# USB_OTG.net
KiCad netlist of a schematic drawn in Altium Designer
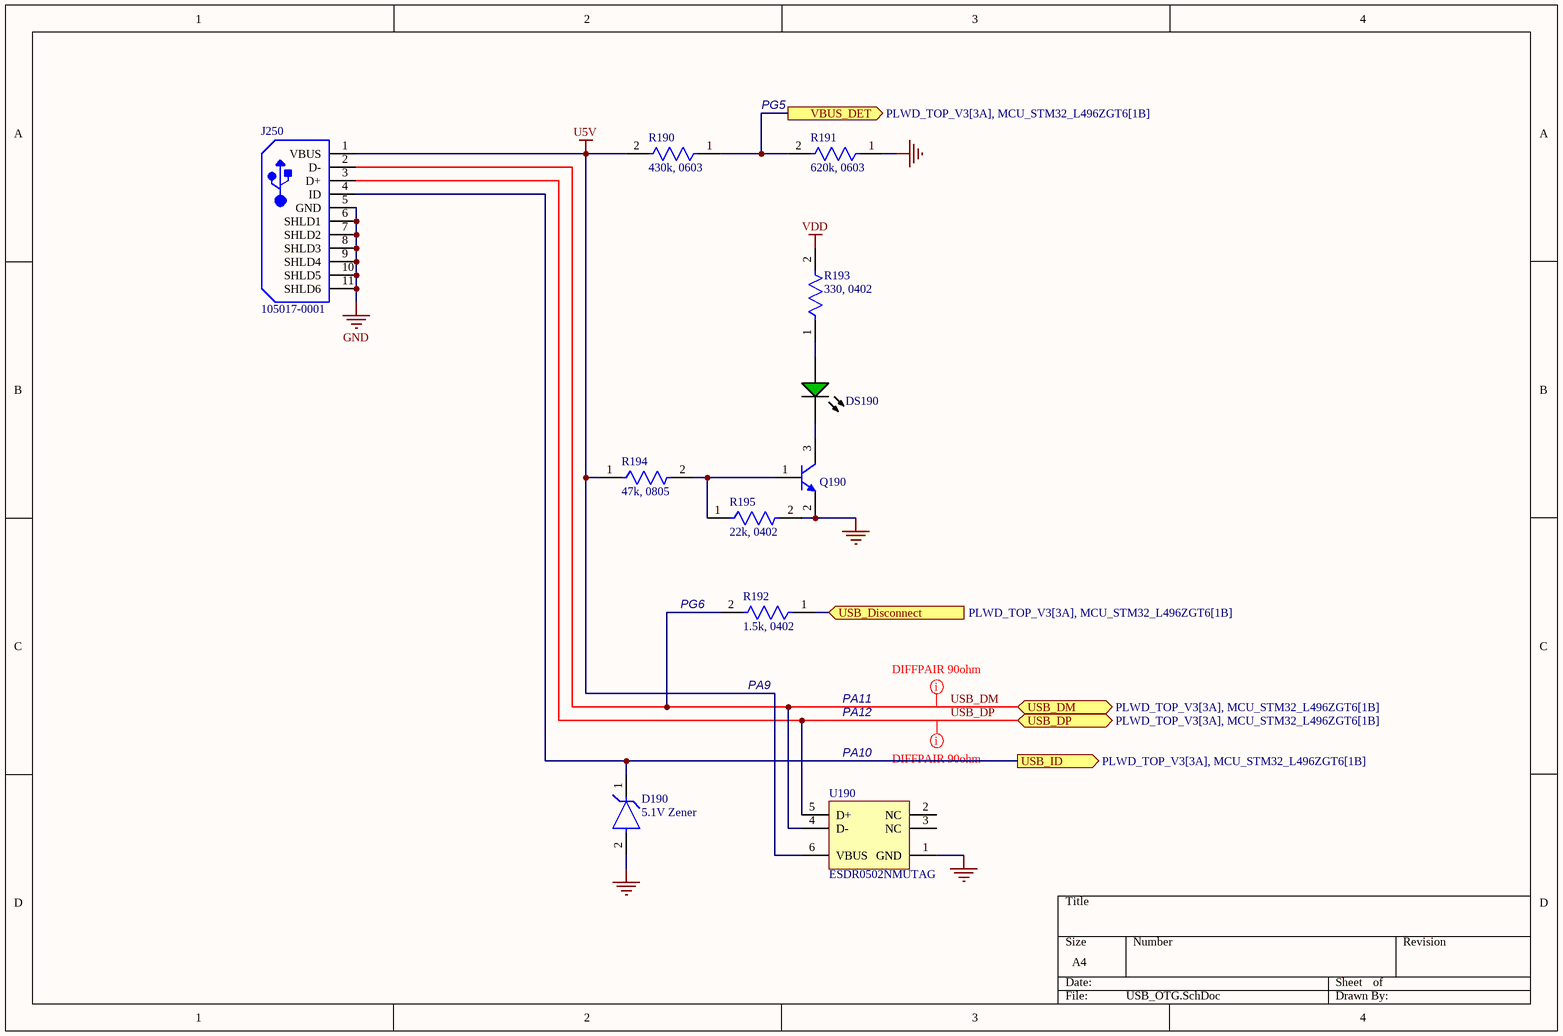
[diagram p0: USB_OTG.SchDoc]

(export (version "E")
  (design (tool "Eeschema 10.0.6"))
  (components
    (comp (ref "D190")
      (value "5.1V Zener")
      (footprint "FP-SOD123-MFG")
      (description "DIODE ZENER 5.1V 500MW SOD123")
      (fields
        (field (name "MANUFACTURER PART NUMBER") "BZT52C5V1-7-F")
        (field (name "OCTOPART") "https://octopart.com/bzt52c5v1-7-f-diodes+inc.-326718")
      )
      (libsource (lib "Altium Content Vault") (part "f813f71cba58e380607f5dd3caf9714"))
    )
    (comp (ref "DS190")
      (value "LTST-C190GKT")
      (footprint "LTST-C190GKT_V")
      (description "LED Uni-Color Green, 100 mW, 30 mA, -55 to 85 degC, 2-Pin SMD, RoHS, Tape and Reel")
      (fields (field (name "POWER") "100mW") (field (name "MANUFACTURER") "Lite-On"))
      (libsource (lib "Carleton University") (part "LED-GREEN-AK-2"))
    )
    (comp (ref "J250")
      (value "105017-0001")
      (footprint "USB-MICRO-B_V")
      (fields (field (name "MANUFACTURER") "Molex"))
      (libsource (lib "Altium Content Vault") (part "USB-5-6SHLD"))
    )
    (comp (ref "Q190")
      (value "SBC817-40LT3G")
      (footprint "ONSC-SOT-23-3-318-08_V")
      (description "General Purpose Transistor, NPN Silicon, 3-Pin SOT-23, Pb-Free, Tape and Reel")
      (fields (field (name "MANUFACTURER") "On Semiconductor"))
      (libsource (lib "Altium Content Vault") (part "ONSC-NPN-B1E2C3-3"))
    )
    (comp (ref "R190")
      (value "430k, 0603")
      (footprint "FP-ESR03-IPC_C")
      (description "430kΩ ±5% 0.25W 0603 Anti-Surge Chip Resistor AEC-Q200")
      (fields (field (name "TOLERANCE") "5%"))
      (libsource (lib "Altium Content Vault") (part "1029c3af85768c4190bb7ad29bc67b5"))
    )
    (comp (ref "R191")
      (value "620k, 0603")
      (footprint "FP-CRCW0603-e3-MFG")
      (description "RES Thick Film, 620kΩ, 5%, 0.1W, 200ppm/°C, 0603")
      (fields (field (name "TOLERANCE") "5%"))
      (libsource (lib "Altium Content Vault") (part "1029c3af85768c4190bb7ad29bc67b5"))
    )
    (comp (ref "R192")
      (value "1.5k, 0402")
      (footprint "FP-RT0402-MFG")
      (description "RT0402DRE071K5L     RES SMD 1.5K OHM 0.5% 1/16W 0402")
      (fields
        (field (name "OCTOPART") "https://octopart.com/rt0402dre071k5l-yageo-1450177")
        (field (name "MANUFACTURER PART NUMBER") "RT0402DRE071K5L")
      )
      (libsource (lib "Altium Content Vault") (part "1029c3af85768c4190bb7ad29bc67b5"))
    )
    (comp (ref "R193")
      (value "330, 0402")
      (footprint "FP-RG1005-MFG")
      (fields (field (name "TOLERANCE") "0.1%"))
      (libsource (lib "Altium Content Vault") (part "1029c3af85768c4190bb7ad29bc67b5"))
    )
    (comp (ref "R194")
      (value "47k, 0805")
      (footprint "FP-CRCW0805-HPe3-IPC_A")
      (description "RES Thick Film, 47kΩ, 1%, 0.5W, 100ppm/°C, 0805")
      (fields (field (name "TOLERANCE") "1%"))
      (libsource (lib "Altium Content Vault") (part "1029c3af85768c4190bb7ad29bc67b5"))
    )
    (comp (ref "R195")
      (value "22k, 0402")
      (footprint "FP-RT0402-MFG")
      (description "RES SMD 22K OHM 0.1% 1/16W 0402")
      (fields
        (field (name "OCTOPART") "https://octopart.com/rt0402brd0722kl-yageo-1219504")
        (field (name "MANUFACTURER") "Yageo")
      )
      (libsource (lib "Altium Content Vault") (part "1029c3af85768c4190bb7ad29bc67b5"))
    )
    (comp (ref "U190")
      (value "ESDR0502NMUTAG")
      (footprint "ONSC-UDFN-6-517AA-01_V")
      (fields (field (name "MANUFACTURER") "On Semiconductor"))
      (libsource (lib "Altium Content Vault") (part "ONSC-ESDR0502N-UDFN-6-517AA-01"))
    )
  )
  (nets
    (net (code "1") (name "/USB_DM") (class "Default")
      (node (ref "J250") (pin "2") (pinfunction "D-_2") (pintype "passive"))
      (node (ref "R192") (pin "2") (pinfunction "2_2") (pintype "passive"))
      (node (ref "U190") (pin "4") (pinfunction "D-_4") (pintype "passive"))
    )
    (net (code "2") (name "/USB_DP") (class "Default")
      (node (ref "J250") (pin "3") (pinfunction "D+_3") (pintype "passive"))
      (node (ref "U190") (pin "5") (pinfunction "D+_5") (pintype "passive"))
    )
    (net (code "3") (name "/USB_Disconnect") (class "Default")
      (node (ref "R192") (pin "1") (pinfunction "1_1") (pintype "passive"))
    )
    (net (code "4") (name "/USB_ID") (class "Default")
      (node (ref "D190") (pin "1") (pinfunction "C_1") (pintype "passive"))
      (node (ref "J250") (pin "4") (pinfunction "ID_4") (pintype "passive"))
    )
    (net (code "5") (name "/VBUS_DET") (class "Default")
      (node (ref "R190") (pin "1") (pinfunction "1_1") (pintype "passive"))
      (node (ref "R191") (pin "2") (pinfunction "2_2") (pintype "passive"))
    )
    (net (code "6") (name "GND") (class "Default")
      (node (ref "D190") (pin "2") (pinfunction "A_2") (pintype "passive"))
      (node (ref "J250") (pin "10") (pinfunction "SHLD5_10") (pintype "passive"))
      (node (ref "J250") (pin "11") (pinfunction "SHLD6_11") (pintype "passive"))
      (node (ref "J250") (pin "5") (pinfunction "GND_5") (pintype "passive"))
      (node (ref "J250") (pin "6") (pinfunction "SHLD1_6") (pintype "passive"))
      (node (ref "J250") (pin "7") (pinfunction "SHLD2_7") (pintype "passive"))
      (node (ref "J250") (pin "8") (pinfunction "SHLD3_8") (pintype "passive"))
      (node (ref "J250") (pin "9") (pinfunction "SHLD4_9") (pintype "passive"))
      (node (ref "Q190") (pin "2") (pinfunction "E_2") (pintype "passive"))
      (node (ref "R191") (pin "1") (pinfunction "1_1") (pintype "passive"))
      (node (ref "R195") (pin "2") (pinfunction "2_2") (pintype "passive"))
      (node (ref "U190") (pin "1") (pinfunction "GND_1") (pintype "power_in"))
    )
    (net (code "7") (name "Net-(DS190-A)") (class "Default")
      (node (ref "DS190") (pin "1") (pinfunction "A_1") (pintype "passive"))
      (node (ref "R193") (pin "1") (pinfunction "1_1") (pintype "passive"))
    )
    (net (code "8") (name "Net-(DS190-K)") (class "Default")
      (node (ref "DS190") (pin "2") (pinfunction "K_2") (pintype "passive"))
      (node (ref "Q190") (pin "3") (pinfunction "C_3") (pintype "passive"))
    )
    (net (code "9") (name "Net-(Q190-B)") (class "Default")
      (node (ref "Q190") (pin "1") (pinfunction "B_1") (pintype "passive"))
      (node (ref "R194") (pin "2") (pinfunction "2_2") (pintype "passive"))
      (node (ref "R195") (pin "1") (pinfunction "1_1") (pintype "passive"))
    )
    (net (code "10") (name "U5V") (class "Default")
      (node (ref "J250") (pin "1") (pinfunction "VBUS_1") (pintype "passive"))
      (node (ref "R190") (pin "2") (pinfunction "2_2") (pintype "passive"))
      (node (ref "R194") (pin "1") (pinfunction "1_1") (pintype "passive"))
      (node (ref "U190") (pin "6") (pinfunction "VBUS_6") (pintype "power_in"))
    )
    (net (code "11") (name "VDD") (class "Default")
      (node (ref "R193") (pin "2") (pinfunction "2_2") (pintype "passive"))
    )
    (net (code "12") (name "unconnected-(U190-NC-Pad2)") (class "Default")
      (node (ref "U190") (pin "2") (pinfunction "NC_2") (pintype "passive"))
    )
    (net (code "13") (name "unconnected-(U190-NC-Pad3)") (class "Default")
      (node (ref "U190") (pin "3") (pinfunction "NC_3") (pintype "passive"))
    )
  )
)
